# 04_-_USB.net
KiCad netlist of a schematic drawn in Altium Designer
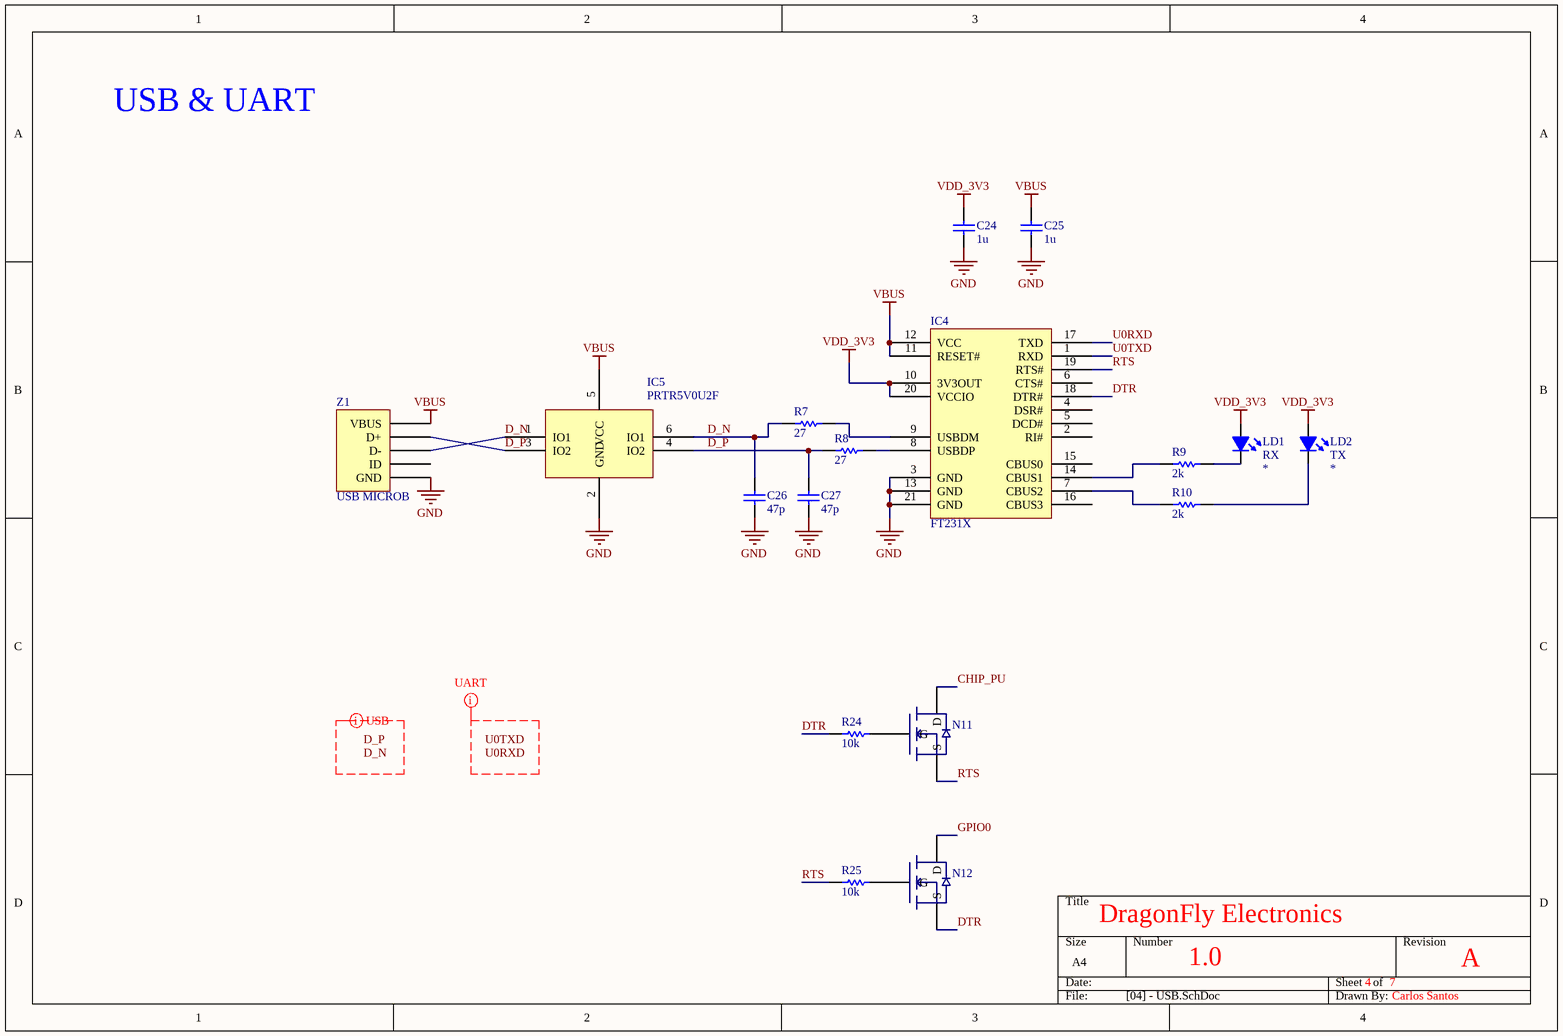
[diagram p0: [04] - USB.SchDoc]

(export (version "E")
  (design (tool "Eeschema 10.0.6"))
  (components
    (comp (ref "C24")
      (value "1u")
      (footprint "0402 - Capacitor")
      (fields (field (name "Comment") "Capacitor"))
      (libsource (lib "Mine") (part "Capacitor"))
    )
    (comp (ref "C25")
      (value "1u")
      (footprint "0402 - Capacitor")
      (fields (field (name "Comment") "Capacitor"))
      (libsource (lib "Mine") (part "Capacitor"))
    )
    (comp (ref "C26")
      (value "47p")
      (footprint "0402 - Capacitor")
      (fields (field (name "Comment") "Capacitor"))
      (libsource (lib "Mine") (part "Capacitor"))
    )
    (comp (ref "C27")
      (value "47p")
      (footprint "0402 - Capacitor")
      (fields (field (name "Comment") "Capacitor"))
      (libsource (lib "Mine") (part "Capacitor"))
    )
    (comp (ref "IC4")
      (value "FT231X")
      (footprint "QFN20-127P600-8N")
      (fields (field (name "DIGIKEY PART #") "768-1128-1-ND"))
      (libsource (lib "Mine") (part "FT231X"))
    )
    (comp (ref "IC5")
      (value "PRTR5V0U2F")
      (footprint "SOT886")
      (fields (field (name "DIGIKEY PART #") "1727-4161-6-ND"))
      (libsource (lib "Mine") (part "PRTR5V0U2F"))
    )
    (comp (ref "LD1")
      (value "Led")
      (footprint "0402 - Led")
      (fields (field (name "COLOR") "RX") (field (name "VF") "*"))
      (libsource (lib "Mine") (part "Led"))
    )
    (comp (ref "LD2")
      (value "Led")
      (footprint "0402 - Led")
      (fields (field (name "COLOR") "TX") (field (name "VF") "*"))
      (libsource (lib "Mine") (part "Led"))
    )
    (comp (ref "N11") (value "N-MOSFET") (footprint "DFN1006-3") (libsource (lib "Mine") (part "N-MOSFET")))
    (comp (ref "N12") (value "N-MOSFET") (footprint "DFN1006-3") (libsource (lib "Mine") (part "N-MOSFET")))
    (comp (ref "R7")
      (value "27")
      (footprint "0402 - Resistor")
      (fields (field (name "Comment") "Resistor"))
      (libsource (lib "Mine") (part "Resistor"))
    )
    (comp (ref "R8")
      (value "27")
      (footprint "0402 - Resistor")
      (fields (field (name "Comment") "Resistor"))
      (libsource (lib "Mine") (part "Resistor"))
    )
    (comp (ref "R9")
      (value "2k")
      (footprint "0402 - Resistor")
      (fields (field (name "Comment") "Resistor"))
      (libsource (lib "Mine") (part "Resistor"))
    )
    (comp (ref "R10")
      (value "2k")
      (footprint "0402 - Resistor")
      (fields (field (name "Comment") "Resistor"))
      (libsource (lib "Mine") (part "Resistor"))
    )
    (comp (ref "R24")
      (value "10k")
      (footprint "0402 - Resistor")
      (fields (field (name "Comment") "Resistor"))
      (libsource (lib "Mine") (part "Resistor"))
    )
    (comp (ref "R25")
      (value "10k")
      (footprint "0402 - Resistor")
      (fields (field (name "Comment") "Resistor"))
      (libsource (lib "Mine") (part "Resistor"))
    )
    (comp (ref "Z1")
      (value "USB MICROB")
      (footprint "USB - microB")
      (description "609-4613-1-ND")
      (libsource (lib "Mine") (part "USB - microB"))
    )
  )
  (nets
    (net (code "1") (name "/CHIP_PU") (class "Default")
      (node (ref "N11") (pin "3") (pinfunction "D_3") (pintype "passive"))
    )
    (net (code "2") (name "/DTR") (class "Default")
      (node (ref "IC4") (pin "18") (pinfunction "DTR#_18") (pintype "passive"))
      (node (ref "N12") (pin "1") (pinfunction "S_1") (pintype "passive"))
      (node (ref "R24") (pin "1") (pinfunction "1_1") (pintype "passive"))
    )
    (net (code "3") (name "/D_N") (class "Default")
      (node (ref "C26") (pin "2") (pinfunction "2_2") (pintype "passive"))
      (node (ref "IC5") (pin "1") (pinfunction "IO1_1") (pintype "passive"))
      (node (ref "IC5") (pin "6") (pinfunction "IO1_6") (pintype "passive"))
      (node (ref "R7") (pin "1") (pinfunction "1_1") (pintype "passive"))
      (node (ref "Z1") (pin "2") (pinfunction "D-_2") (pintype "passive"))
    )
    (net (code "4") (name "/D_P") (class "Default")
      (node (ref "C27") (pin "2") (pinfunction "2_2") (pintype "passive"))
      (node (ref "IC5") (pin "3") (pinfunction "IO2_3") (pintype "passive"))
      (node (ref "IC5") (pin "4") (pinfunction "IO2_4") (pintype "passive"))
      (node (ref "R8") (pin "1") (pinfunction "1_1") (pintype "passive"))
      (node (ref "Z1") (pin "3") (pinfunction "D+_3") (pintype "passive"))
    )
    (net (code "5") (name "/GPIO0") (class "Default")
      (node (ref "N12") (pin "3") (pinfunction "D_3") (pintype "passive"))
    )
    (net (code "6") (name "/RTS") (class "Default")
      (node (ref "IC4") (pin "19") (pinfunction "RTS#_19") (pintype "passive"))
      (node (ref "N11") (pin "1") (pinfunction "S_1") (pintype "passive"))
      (node (ref "R25") (pin "1") (pinfunction "1_1") (pintype "passive"))
    )
    (net (code "7") (name "/U0RXD") (class "Default")
      (node (ref "IC4") (pin "17") (pinfunction "TXD_17") (pintype "passive"))
    )
    (net (code "8") (name "/U0TXD") (class "Default")
      (node (ref "IC4") (pin "1") (pinfunction "RXD_1") (pintype "passive"))
    )
    (net (code "9") (name "GND") (class "Default")
      (node (ref "C24") (pin "1") (pinfunction "1_1") (pintype "passive"))
      (node (ref "C25") (pin "1") (pinfunction "1_1") (pintype "passive"))
      (node (ref "C26") (pin "1") (pinfunction "1_1") (pintype "passive"))
      (node (ref "C27") (pin "1") (pinfunction "1_1") (pintype "passive"))
      (node (ref "IC4") (pin "13") (pinfunction "GND_13") (pintype "passive"))
      (node (ref "IC4") (pin "21") (pinfunction "GND_21") (pintype "passive"))
      (node (ref "IC4") (pin "3") (pinfunction "GND_3") (pintype "passive"))
      (node (ref "IC5") (pin "2") (pinfunction "GND_2") (pintype "passive"))
      (node (ref "Z1") (pin "5") (pinfunction "GND_5") (pintype "passive"))
    )
    (net (code "10") (name "Net-(IC4-CBUS1)") (class "Default")
      (node (ref "IC4") (pin "14") (pinfunction "CBUS1_14") (pintype "passive"))
      (node (ref "R9") (pin "1") (pinfunction "1_1") (pintype "passive"))
    )
    (net (code "11") (name "Net-(IC4-CBUS2)") (class "Default")
      (node (ref "IC4") (pin "7") (pinfunction "CBUS2_7") (pintype "passive"))
      (node (ref "R10") (pin "1") (pinfunction "1_1") (pintype "passive"))
    )
    (net (code "12") (name "Net-(IC4-USBDM)") (class "Default")
      (node (ref "IC4") (pin "9") (pinfunction "USBDM_9") (pintype "passive"))
      (node (ref "R7") (pin "2") (pinfunction "2_2") (pintype "passive"))
    )
    (net (code "13") (name "Net-(IC4-USBDP)") (class "Default")
      (node (ref "IC4") (pin "8") (pinfunction "USBDP_8") (pintype "passive"))
      (node (ref "R8") (pin "2") (pinfunction "2_2") (pintype "passive"))
    )
    (net (code "14") (name "Net-(LD1-K)") (class "Default")
      (node (ref "LD1") (pin "2") (pinfunction "K_2") (pintype "passive"))
      (node (ref "R9") (pin "2") (pinfunction "2_2") (pintype "passive"))
    )
    (net (code "15") (name "Net-(LD2-K)") (class "Default")
      (node (ref "LD2") (pin "2") (pinfunction "K_2") (pintype "passive"))
      (node (ref "R10") (pin "2") (pinfunction "2_2") (pintype "passive"))
    )
    (net (code "16") (name "Net-(N11-G)") (class "Default")
      (node (ref "N11") (pin "2") (pinfunction "G_2") (pintype "passive"))
      (node (ref "R24") (pin "2") (pinfunction "2_2") (pintype "passive"))
    )
    (net (code "17") (name "Net-(N12-G)") (class "Default")
      (node (ref "N12") (pin "2") (pinfunction "G_2") (pintype "passive"))
      (node (ref "R25") (pin "2") (pinfunction "2_2") (pintype "passive"))
    )
    (net (code "18") (name "VBUS") (class "Default")
      (node (ref "C25") (pin "2") (pinfunction "2_2") (pintype "passive"))
      (node (ref "IC4") (pin "11") (pinfunction "RESET#_11") (pintype "passive"))
      (node (ref "IC4") (pin "12") (pinfunction "VCC_12") (pintype "passive"))
      (node (ref "IC5") (pin "5") (pinfunction "VCC_5") (pintype "passive"))
      (node (ref "Z1") (pin "1") (pinfunction "VBUS_1") (pintype "passive"))
    )
    (net (code "19") (name "VDD_3V3") (class "Default")
      (node (ref "C24") (pin "2") (pinfunction "2_2") (pintype "passive"))
      (node (ref "IC4") (pin "10") (pinfunction "3V3OUT_10") (pintype "passive"))
      (node (ref "IC4") (pin "20") (pinfunction "VCCIO_20") (pintype "passive"))
      (node (ref "LD1") (pin "1") (pinfunction "A_1") (pintype "passive"))
      (node (ref "LD2") (pin "1") (pinfunction "A_1") (pintype "passive"))
    )
    (net (code "20") (name "unconnected-(IC4-CBUS0-Pad15)") (class "Default")
      (node (ref "IC4") (pin "15") (pinfunction "CBUS0_15") (pintype "passive"))
    )
    (net (code "21") (name "unconnected-(IC4-CBUS3-Pad16)") (class "Default")
      (node (ref "IC4") (pin "16") (pinfunction "CBUS3_16") (pintype "passive"))
    )
    (net (code "22") (name "unconnected-(IC4-CTS#-Pad6)") (class "Default")
      (node (ref "IC4") (pin "6") (pinfunction "CTS#_6") (pintype "passive"))
    )
    (net (code "23") (name "unconnected-(IC4-DCD#-Pad5)") (class "Default")
      (node (ref "IC4") (pin "5") (pinfunction "DCD#_5") (pintype "passive"))
    )
    (net (code "24") (name "unconnected-(IC4-DSR#-Pad4)") (class "Default")
      (node (ref "IC4") (pin "4") (pinfunction "DSR#_4") (pintype "passive"))
    )
    (net (code "25") (name "unconnected-(IC4-RI#-Pad2)") (class "Default")
      (node (ref "IC4") (pin "2") (pinfunction "RI#_2") (pintype "passive"))
    )
    (net (code "26") (name "unconnected-(Z1-ID-Pad4)") (class "Default")
      (node (ref "Z1") (pin "4") (pinfunction "ID_4") (pintype "passive"))
    )
  )
)
